# Sch_PowerSupply7805.net
KiCad netlist of a schematic drawn in Altium Designer
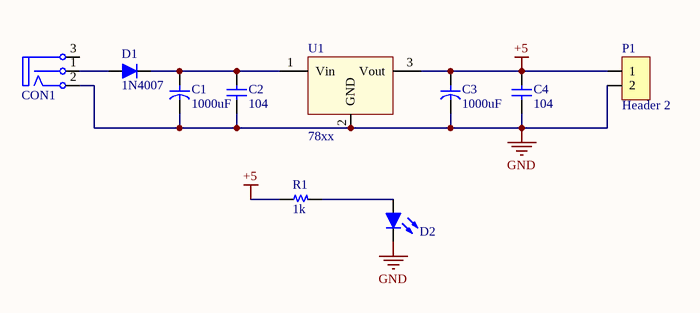
[diagram p0: Sch_PowerSupply7805.SchDoc]

(export (version "E")
  (design (tool "Eeschema 10.0.6"))
  (components
    (comp (ref "C1")
      (value "1000uF")
      (footprint "CYL/D.400/LS.200")
      (description "Capacitor pol")
      (libsource (lib "chipfc_libs") (part "Capacitor"))
    )
    (comp (ref "C2")
      (value "104")
      (footprint "CAP Ceramic/W300")
      (description "Capacitor non-pol")
      (libsource (lib "chipfc_libs") (part "Capacitor NP"))
    )
    (comp (ref "C3")
      (value "1000uF")
      (footprint "CYL/D.400/LS.200")
      (description "Capacitor pol")
      (libsource (lib "chipfc_libs") (part "Capacitor"))
    )
    (comp (ref "C4")
      (value "104")
      (footprint "CAP Ceramic/W300")
      (description "Capacitor non-pol")
      (libsource (lib "chipfc_libs") (part "Capacitor NP"))
    )
    (comp (ref "CON1")
      (value "CON DC PWR")
      (footprint "CONN/DC/PWR/5.0MM")
      (description "DC input connector")
      (libsource (lib "connectors") (part "CON DC PWR"))
    )
    (comp (ref "D1")
      (value "1N4007")
      (footprint "DO-41")
      (description "Default Diode")
      (libsource (lib "chipfc_libs") (part "Diode"))
    )
    (comp (ref "D2")
      (value "Led")
      (footprint "LED 5MM - RED")
      (description "Typical LED")
      (libsource (lib "led") (part "Led"))
    )
    (comp (ref "P1")
      (value "Header 2")
      (footprint "HDR/Terminal/2")
      (description "Header, 2-Pin")
      (libsource (lib "connectors") (part "Header 2"))
    )
    (comp (ref "R1")
      (value "1k")
      (footprint "R 1/4W/300")
      (description "Resistor")
      (libsource (lib "chipfc_libs") (part "Resistor"))
    )
    (comp (ref "U1")
      (value "78xx")
      (footprint "TO-220")
      (description "LDO Fixed Voltage regulator")
      (libsource (lib "chipfc_libs") (part "78xx"))
    )
  )
  (nets
    (net (code "1") (name "+5") (class "Default")
      (node (ref "C3") (pin "1") (pinfunction "1_1") (pintype "passive"))
      (node (ref "C4") (pin "1") (pinfunction "1_1") (pintype "passive"))
      (node (ref "P1") (pin "1") (pinfunction "1_1") (pintype "passive"))
      (node (ref "R1") (pin "1") (pinfunction "1_1") (pintype "passive"))
      (node (ref "U1") (pin "3") (pinfunction "Vout_3") (pintype "passive"))
    )
    (net (code "2") (name "GND") (class "Default")
      (node (ref "C1") (pin "2") (pinfunction "2_2") (pintype "passive"))
      (node (ref "C2") (pin "2") (pinfunction "2_2") (pintype "passive"))
      (node (ref "C3") (pin "2") (pinfunction "2_2") (pintype "passive"))
      (node (ref "C4") (pin "2") (pinfunction "2_2") (pintype "passive"))
      (node (ref "CON1") (pin "2") (pinfunction "T_2") (pintype "passive"))
      (node (ref "D2") (pin "2") (pinfunction "K_2") (pintype "passive"))
      (node (ref "P1") (pin "2") (pinfunction "2_2") (pintype "passive"))
      (node (ref "U1") (pin "2") (pinfunction "GND_2") (pintype "passive"))
    )
    (net (code "3") (name "Net-(CON1-S)") (class "Default")
      (node (ref "CON1") (pin "1") (pinfunction "S_1") (pintype "power_in"))
      (node (ref "D1") (pin "1") (pinfunction "A_1") (pintype "passive"))
    )
    (net (code "4") (name "Net-(D1-K)") (class "Default")
      (node (ref "C1") (pin "1") (pinfunction "1_1") (pintype "passive"))
      (node (ref "C2") (pin "1") (pinfunction "1_1") (pintype "passive"))
      (node (ref "D1") (pin "2") (pinfunction "K_2") (pintype "passive"))
      (node (ref "U1") (pin "1") (pinfunction "Vin_1") (pintype "power_in"))
    )
    (net (code "5") (name "Net-(D2-A)") (class "Default")
      (node (ref "D2") (pin "1") (pinfunction "A_1") (pintype "passive"))
      (node (ref "R1") (pin "2") (pinfunction "2_2") (pintype "passive"))
    )
    (net (code "6") (name "unconnected-(CON1-TN-Pad3)") (class "Default")
      (node (ref "CON1") (pin "3") (pinfunction "TN_3") (pintype "passive"))
    )
  )
)
